# pilote_poele_2020-12-14_11-01-37.net
KiCad netlist of a schematic drawn in EasyEDA
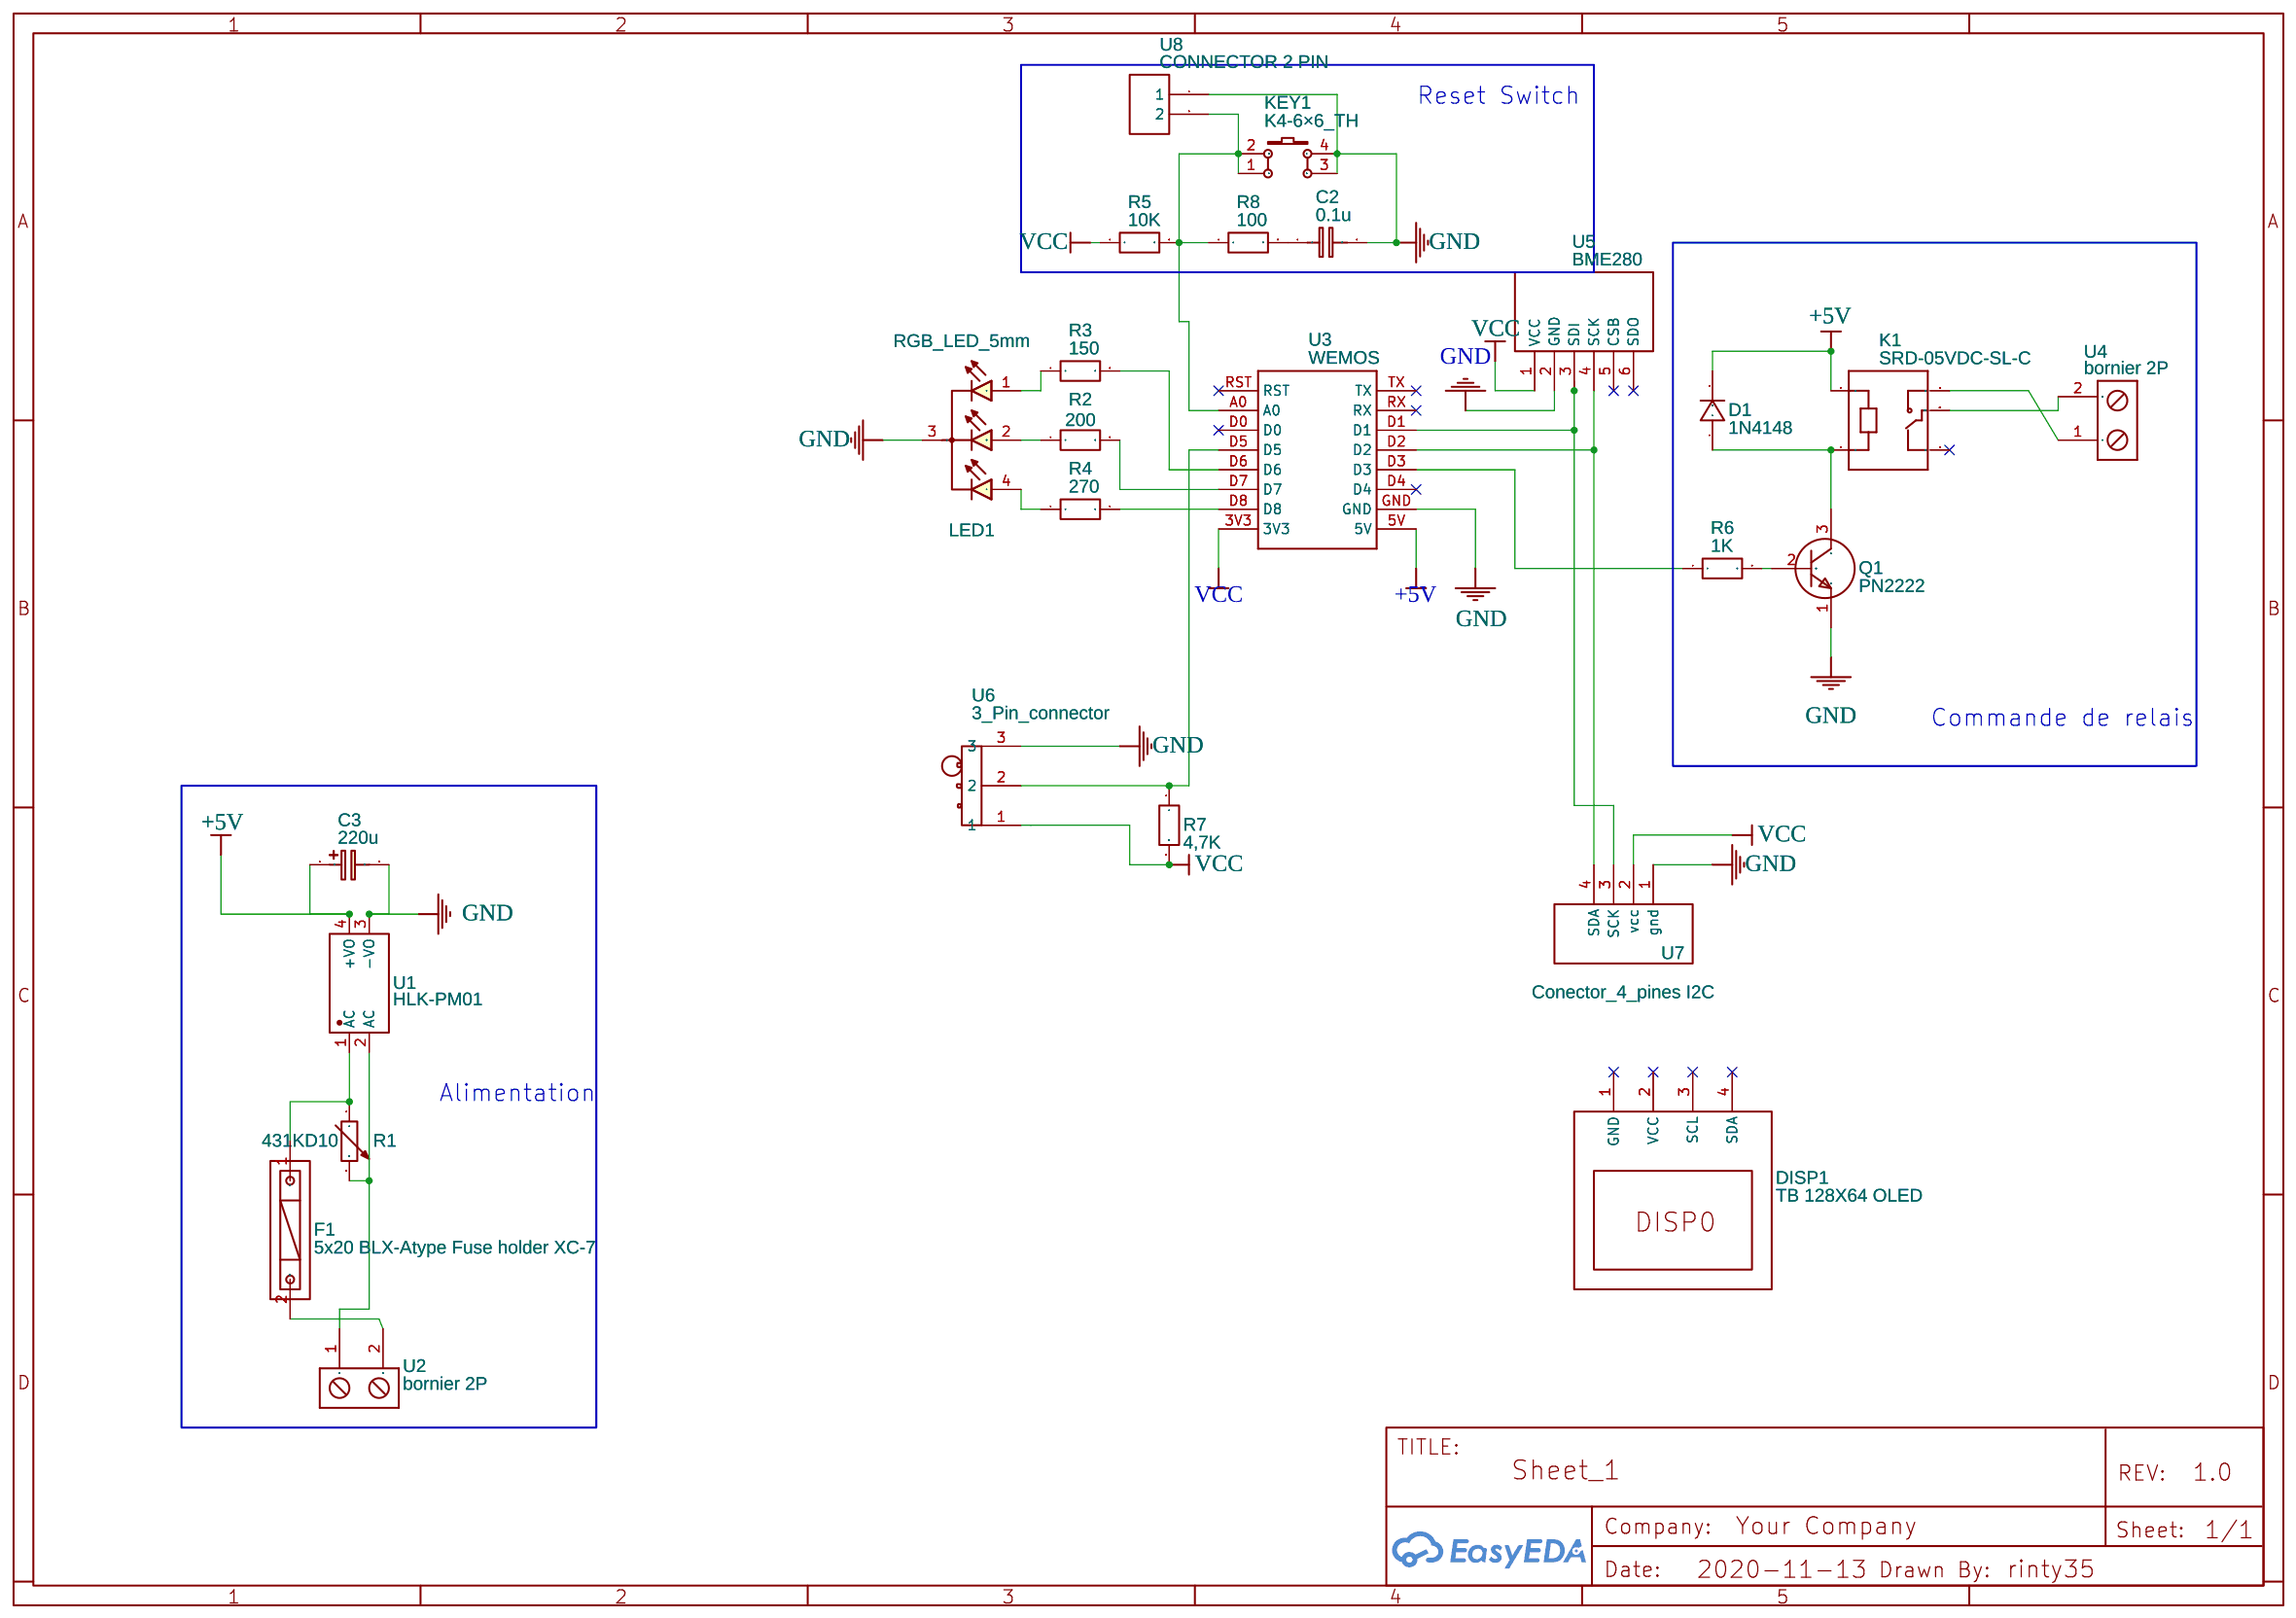
[diagram p0: schematic sheet]

(export (version "E")
  (design (tool "Eeschema 10.0.6"))
  (components
    (comp (ref "C2") (value "0.1u") (libsource (lib "") (part "C_0603_EU")))
    (comp (ref "C3") (value "220u") (libsource (lib "") (part "CE_TH_D4.0×F1.5_EU")))
    (comp (ref "D1")
      (value "1N4148")
      (fields (field (name "BOM_Supplier Part") "C14516"))
      (libsource (lib "") (part "1N4148"))
    )
    (comp (ref "DISP1") (value "TB 128X64 OLED") (libsource (lib "") (part "TB 128X64 OLED")))
    (comp (ref "F1")
      (value "5x20 BLX-Atype Fuse holder XC-7")
      (fields (field (name "BOM_Supplier Part") "C3131"))
      (libsource (lib "") (part "5x20 BLX-Atype Fuse holder XC-7"))
    )
    (comp (ref "K1") (value "SRD-05VDC-SL-C") (libsource (lib "") (part "SRD-05VDC-SL-C")))
    (comp (ref "KEY1")
      (value "K4-6×6_TH")
      (fields
        (field (name "BOM_Manufacturer Part") "K2-1102DP-E4SW-04")
        (field (name "BOM_Supplier Part") "C136684")
      )
      (libsource (lib "") (part "K4-6×6_TH"))
    )
    (comp (ref "LED1")
      (value "RGB_LED_5mm")
      (fields (field (name "BOM_Manufacturer Part") "φ5 RGB LED") (field (name "BOM_Supplier Part") "C32985"))
      (libsource (lib "") (part "RGB_LED_5mm"))
    )
    (comp (ref "Q1") (value "PN2222") (libsource (lib "") (part "PN2222")))
    (comp (ref "R1")
      (value "431KD10")
      (fields (field (name "BOM_Supplier Part") "C123332"))
      (libsource (lib "") (part "431KD10"))
    )
    (comp (ref "R2") (value "200") (libsource (lib "") (part "R_AXIAL-0.5_EU")))
    (comp (ref "R3") (value "150") (libsource (lib "") (part "R_AXIAL-0.5_EU")))
    (comp (ref "R4") (value "270") (libsource (lib "") (part "R_AXIAL-0.5_EU")))
    (comp (ref "R5") (value "10K") (libsource (lib "") (part "R_AXIAL-0.5_EU")))
    (comp (ref "R6") (value "1K") (libsource (lib "") (part "R_AXIAL-0.5_EU")))
    (comp (ref "R7") (value "4,7K") (libsource (lib "") (part "R_0603_EU")))
    (comp (ref "R8") (value "100") (libsource (lib "") (part "R_AXIAL-0.5_EU")))
    (comp (ref "U1")
      (value "HLK-PM01")
      (fields (field (name "BOM_Supplier Part") "C209903"))
      (libsource (lib "") (part "HLK-PM01"))
    )
    (comp (ref "U2")
      (value "bornier 2P")
      (fields (field (name "BOM_Manufacturer Part") "bornier"))
      (libsource (lib "") (part "bornier 2P_1"))
    )
    (comp (ref "U3") (value "WEMOS") (libsource (lib "") (part "WEMOS")))
    (comp (ref "U4")
      (value "bornier 2P")
      (fields (field (name "BOM_Manufacturer Part") "bornier"))
      (libsource (lib "") (part "bornier 2P"))
    )
    (comp (ref "U5") (value "BME280") (libsource (lib "") (part "BME280")))
    (comp (ref "U6")
      (value "3_Pin_connector")
      (fields (field (name "BOM_Manufacturer Part") "pin 3"))
      (libsource (lib "") (part "3_Pin_connector"))
    )
    (comp (ref "U7") (value "Conector_4_pines I2C") (libsource (lib "") (part "Conector_4_pines")))
    (comp (ref "U8") (value "CONNECTOR 2 PIN") (libsource (lib "") (part "CONNECTOR 2 PIN")))
  )
  (nets
    (net (code "1") (name "+5V") (class "Default")
      (node (ref "C3") (pin "1") (pinfunction "1_1") (pintype "unspecified"))
      (node (ref "D1") (pin "2") (pinfunction "2_2") (pintype "unspecified"))
      (node (ref "K1") (pin "A1") (pinfunction "A1_A1") (pintype "bidirectional"))
      (node (ref "U1") (pin "4") (pinfunction "+VO_4") (pintype "unspecified"))
      (node (ref "U3") (pin "5V") (pinfunction "5V_5V") (pintype "unspecified"))
    )
    (net (code "2") (name "GND") (class "Default")
      (node (ref "C2") (pin "2") (pinfunction "2_2") (pintype "unspecified"))
      (node (ref "C3") (pin "2") (pinfunction "2_2") (pintype "unspecified"))
      (node (ref "KEY1") (pin "3") (pinfunction "3_3") (pintype "unspecified"))
      (node (ref "KEY1") (pin "4") (pinfunction "4_4") (pintype "unspecified"))
      (node (ref "LED1") (pin "3") (pinfunction "3_3") (pintype "unspecified"))
      (node (ref "Q1") (pin "1") (pinfunction "E_1") (pintype "unspecified"))
      (node (ref "U1") (pin "3") (pinfunction "-VO_3") (pintype "unspecified"))
      (node (ref "U3") (pin "GND") (pinfunction "GND_GND") (pintype "unspecified"))
      (node (ref "U5") (pin "2") (pinfunction "GND_2") (pintype "unspecified"))
      (node (ref "U6") (pin "3") (pinfunction "3_3") (pintype "unspecified"))
      (node (ref "U7") (pin "1") (pinfunction "gnd_1") (pintype "unspecified"))
      (node (ref "U8") (pin "1") (pinfunction "1_1") (pintype "unspecified"))
    )
    (net (code "3") (name "Net-(C2-Pad1)") (class "Default")
      (node (ref "C2") (pin "1") (pinfunction "1_1") (pintype "unspecified"))
      (node (ref "R8") (pin "2") (pinfunction "2_2") (pintype "unspecified"))
    )
    (net (code "4") (name "Net-(F1-Pad1)") (class "Default")
      (node (ref "F1") (pin "1") (pinfunction "1_1") (pintype "unspecified"))
      (node (ref "R1") (pin "1") (pinfunction "1_1") (pintype "unspecified"))
      (node (ref "U1") (pin "1") (pinfunction "AC_1") (pintype "unspecified"))
    )
    (net (code "5") (name "Net-(F1-Pad2)") (class "Default")
      (node (ref "F1") (pin "2") (pinfunction "2_2") (pintype "unspecified"))
      (node (ref "U2") (pin "2") (pinfunction "2_2") (pintype "unspecified"))
    )
    (net (code "6") (name "Net-(K1-PadCOM)") (class "Default")
      (node (ref "K1") (pin "COM") (pinfunction "COM_COM") (pintype "bidirectional"))
      (node (ref "U4") (pin "2") (pinfunction "2_2") (pintype "unspecified"))
    )
    (net (code "7") (name "Net-(K1-PadNO)") (class "Default")
      (node (ref "K1") (pin "NO") (pinfunction "NO_NO") (pintype "bidirectional"))
      (node (ref "U4") (pin "1") (pinfunction "1_1") (pintype "unspecified"))
    )
    (net (code "8") (name "Net-(KEY1-Pad1)") (class "Default")
      (node (ref "KEY1") (pin "1") (pinfunction "1_1") (pintype "unspecified"))
      (node (ref "KEY1") (pin "2") (pinfunction "2_2") (pintype "unspecified"))
      (node (ref "R5") (pin "2") (pinfunction "2_2") (pintype "unspecified"))
      (node (ref "R8") (pin "1") (pinfunction "1_1") (pintype "unspecified"))
      (node (ref "U3") (pin "A0") (pinfunction "A0_A0") (pintype "unspecified"))
      (node (ref "U8") (pin "2") (pinfunction "2_2") (pintype "unspecified"))
    )
    (net (code "9") (name "Net-(LED1-Pad1)") (class "Default")
      (node (ref "LED1") (pin "1") (pinfunction "1_1") (pintype "unspecified"))
      (node (ref "R3") (pin "1") (pinfunction "1_1") (pintype "unspecified"))
    )
    (net (code "10") (name "Net-(LED1-Pad2)") (class "Default")
      (node (ref "LED1") (pin "2") (pinfunction "2_2") (pintype "unspecified"))
      (node (ref "R2") (pin "1") (pinfunction "1_1") (pintype "unspecified"))
    )
    (net (code "11") (name "Net-(LED1-Pad4)") (class "Default")
      (node (ref "LED1") (pin "4") (pinfunction "4_4") (pintype "unspecified"))
      (node (ref "R4") (pin "1") (pinfunction "1_1") (pintype "unspecified"))
    )
    (net (code "12") (name "Net-(Q1-B)") (class "Default")
      (node (ref "Q1") (pin "2") (pinfunction "B_2") (pintype "unspecified"))
      (node (ref "R6") (pin "2") (pinfunction "2_2") (pintype "unspecified"))
    )
    (net (code "13") (name "Net-(Q1-C)") (class "Default")
      (node (ref "D1") (pin "1") (pinfunction "1_1") (pintype "unspecified"))
      (node (ref "K1") (pin "A2") (pinfunction "A2_A2") (pintype "bidirectional"))
      (node (ref "Q1") (pin "3") (pinfunction "C_3") (pintype "unspecified"))
    )
    (net (code "14") (name "Net-(R1-Pad2)") (class "Default")
      (node (ref "R1") (pin "2") (pinfunction "2_2") (pintype "unspecified"))
      (node (ref "U1") (pin "2") (pinfunction "AC_2") (pintype "unspecified"))
      (node (ref "U2") (pin "1") (pinfunction "1_1") (pintype "unspecified"))
    )
    (net (code "15") (name "Net-(R2-Pad2)") (class "Default")
      (node (ref "R2") (pin "2") (pinfunction "2_2") (pintype "unspecified"))
      (node (ref "U3") (pin "D7") (pinfunction "D7_D7") (pintype "unspecified"))
    )
    (net (code "16") (name "Net-(R3-Pad2)") (class "Default")
      (node (ref "R3") (pin "2") (pinfunction "2_2") (pintype "unspecified"))
      (node (ref "U3") (pin "D6") (pinfunction "D6_D6") (pintype "unspecified"))
    )
    (net (code "17") (name "Net-(R4-Pad2)") (class "Default")
      (node (ref "R4") (pin "2") (pinfunction "2_2") (pintype "unspecified"))
      (node (ref "U3") (pin "D8") (pinfunction "D8_D8") (pintype "unspecified"))
    )
    (net (code "18") (name "Net-(R6-Pad1)") (class "Default")
      (node (ref "R6") (pin "1") (pinfunction "1_1") (pintype "unspecified"))
      (node (ref "U3") (pin "D3") (pinfunction "D3_D3") (pintype "unspecified"))
    )
    (net (code "19") (name "Net-(R7-Pad1)") (class "Default")
      (node (ref "R7") (pin "1") (pinfunction "1_1") (pintype "unspecified"))
      (node (ref "U3") (pin "D5") (pinfunction "D5_D5") (pintype "unspecified"))
      (node (ref "U6") (pin "2") (pinfunction "2_2") (pintype "unspecified"))
    )
    (net (code "20") (name "Net-(U5-SCK)") (class "Default")
      (node (ref "U3") (pin "D2") (pinfunction "D2_D2") (pintype "unspecified"))
      (node (ref "U5") (pin "4") (pinfunction "SCK_4") (pintype "unspecified"))
      (node (ref "U7") (pin "4") (pinfunction "SDA_4") (pintype "unspecified"))
    )
    (net (code "21") (name "Net-(U5-SDI)") (class "Default")
      (node (ref "U3") (pin "D1") (pinfunction "D1_D1") (pintype "unspecified"))
      (node (ref "U5") (pin "3") (pinfunction "SDI_3") (pintype "unspecified"))
      (node (ref "U7") (pin "3") (pinfunction "SCK_3") (pintype "unspecified"))
    )
    (net (code "22") (name "VCC") (class "Default")
      (node (ref "R5") (pin "1") (pinfunction "1_1") (pintype "unspecified"))
      (node (ref "R7") (pin "2") (pinfunction "2_2") (pintype "unspecified"))
      (node (ref "U3") (pin "3V3") (pinfunction "3V3_3V3") (pintype "unspecified"))
      (node (ref "U5") (pin "1") (pinfunction "VCC_1") (pintype "unspecified"))
      (node (ref "U6") (pin "1") (pinfunction "1_1") (pintype "unspecified"))
      (node (ref "U7") (pin "2") (pinfunction "vcc_2") (pintype "unspecified"))
    )
    (net (code "23") (name "unconnected-(DISP1-GND-Pad1)") (class "Default")
      (node (ref "DISP1") (pin "1") (pinfunction "GND_1") (pintype "unspecified+no_connect"))
    )
    (net (code "24") (name "unconnected-(DISP1-SCL-Pad3)") (class "Default")
      (node (ref "DISP1") (pin "3") (pinfunction "SCL_3") (pintype "unspecified+no_connect"))
    )
    (net (code "25") (name "unconnected-(DISP1-SDA-Pad4)") (class "Default")
      (node (ref "DISP1") (pin "4") (pinfunction "SDA_4") (pintype "unspecified+no_connect"))
    )
    (net (code "26") (name "unconnected-(DISP1-VCC-Pad2)") (class "Default")
      (node (ref "DISP1") (pin "2") (pinfunction "VCC_2") (pintype "unspecified+no_connect"))
    )
    (net (code "27") (name "unconnected-(K1-PadNC)") (class "Default")
      (node (ref "K1") (pin "NC") (pinfunction "NC_NC") (pintype "bidirectional+no_connect"))
    )
    (net (code "28") (name "unconnected-(U3-PadD0)") (class "Default")
      (node (ref "U3") (pin "D0") (pinfunction "D0_D0") (pintype "unspecified+no_connect"))
    )
    (net (code "29") (name "unconnected-(U3-PadD4)") (class "Default")
      (node (ref "U3") (pin "D4") (pinfunction "D4_D4") (pintype "unspecified+no_connect"))
    )
    (net (code "30") (name "unconnected-(U3-PadRST)") (class "Default")
      (node (ref "U3") (pin "RST") (pinfunction "RST_RST") (pintype "unspecified+no_connect"))
    )
    (net (code "31") (name "unconnected-(U3-PadRX)") (class "Default")
      (node (ref "U3") (pin "RX") (pinfunction "RX_RX") (pintype "unspecified+no_connect"))
    )
    (net (code "32") (name "unconnected-(U3-PadTX)") (class "Default")
      (node (ref "U3") (pin "TX") (pinfunction "TX_TX") (pintype "unspecified+no_connect"))
    )
    (net (code "33") (name "unconnected-(U5-CSB-Pad5)") (class "Default")
      (node (ref "U5") (pin "5") (pinfunction "CSB_5") (pintype "unspecified+no_connect"))
    )
    (net (code "34") (name "unconnected-(U5-SDO-Pad6)") (class "Default")
      (node (ref "U5") (pin "6") (pinfunction "SDO_6") (pintype "unspecified+no_connect"))
    )
  )
)
